# MicroPak-10_Breakout.net
KiCad netlist of a schematic drawn in EAGLE
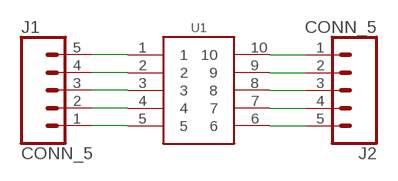
[diagram p0: schematic, sheet 1]

(export (version "E")
  (design (tool "Eeschema 10.0.6"))
  (components
    (comp (ref "J1")
      (value "CONN_5")
      (footprint "eagle-import:1X05")
      (libsource (lib "eagle-import") (part "CONN_5"))
    )
    (comp (ref "J2")
      (value "CONN_5")
      (footprint "eagle-import:1X05")
      (libsource (lib "eagle-import") (part "CONN_5"))
    )
    (comp (ref "U1")
      (value "GEN_10MICROPACK")
      (footprint "eagle-import:MICROPAK_10")
      (libsource (lib "eagle-import") (part "GEN_10MICROPACK"))
    )
  )
  (nets
    (net (code "1") (name "Net-(J1-Pad1)") (class "Default")
      (node (ref "J1") (pin "1") (pinfunction "1_1") (pintype "passive"))
      (node (ref "U1") (pin "5") (pinfunction "5_5") (pintype "bidirectional"))
    )
    (net (code "2") (name "Net-(J1-Pad2)") (class "Default")
      (node (ref "J1") (pin "2") (pinfunction "2_2") (pintype "passive"))
      (node (ref "U1") (pin "4") (pinfunction "4_4") (pintype "bidirectional"))
    )
    (net (code "3") (name "Net-(J1-Pad3)") (class "Default")
      (node (ref "J1") (pin "3") (pinfunction "3_3") (pintype "passive"))
      (node (ref "U1") (pin "3") (pinfunction "3_3") (pintype "bidirectional"))
    )
    (net (code "4") (name "Net-(J1-Pad4)") (class "Default")
      (node (ref "J1") (pin "4") (pinfunction "4_4") (pintype "passive"))
      (node (ref "U1") (pin "2") (pinfunction "2_2") (pintype "bidirectional"))
    )
    (net (code "5") (name "Net-(J1-Pad5)") (class "Default")
      (node (ref "J1") (pin "5") (pinfunction "5_5") (pintype "passive"))
      (node (ref "U1") (pin "1") (pinfunction "1_1") (pintype "bidirectional"))
    )
    (net (code "6") (name "Net-(J2-Pad1)") (class "Default")
      (node (ref "J2") (pin "1") (pinfunction "1_1") (pintype "passive"))
      (node (ref "U1") (pin "10") (pinfunction "10_10") (pintype "bidirectional"))
    )
    (net (code "7") (name "Net-(J2-Pad2)") (class "Default")
      (node (ref "J2") (pin "2") (pinfunction "2_2") (pintype "passive"))
      (node (ref "U1") (pin "9") (pinfunction "9_9") (pintype "bidirectional"))
    )
    (net (code "8") (name "Net-(J2-Pad3)") (class "Default")
      (node (ref "J2") (pin "3") (pinfunction "3_3") (pintype "passive"))
      (node (ref "U1") (pin "8") (pinfunction "8_8") (pintype "bidirectional"))
    )
    (net (code "9") (name "Net-(J2-Pad4)") (class "Default")
      (node (ref "J2") (pin "4") (pinfunction "4_4") (pintype "passive"))
      (node (ref "U1") (pin "7") (pinfunction "7_7") (pintype "bidirectional"))
    )
    (net (code "10") (name "Net-(J2-Pad5)") (class "Default")
      (node (ref "J2") (pin "5") (pinfunction "5_5") (pintype "passive"))
      (node (ref "U1") (pin "6") (pinfunction "6_6") (pintype "bidirectional"))
    )
  )
)
